# Keyboard.net
KiCad netlist of a schematic drawn in EAGLE
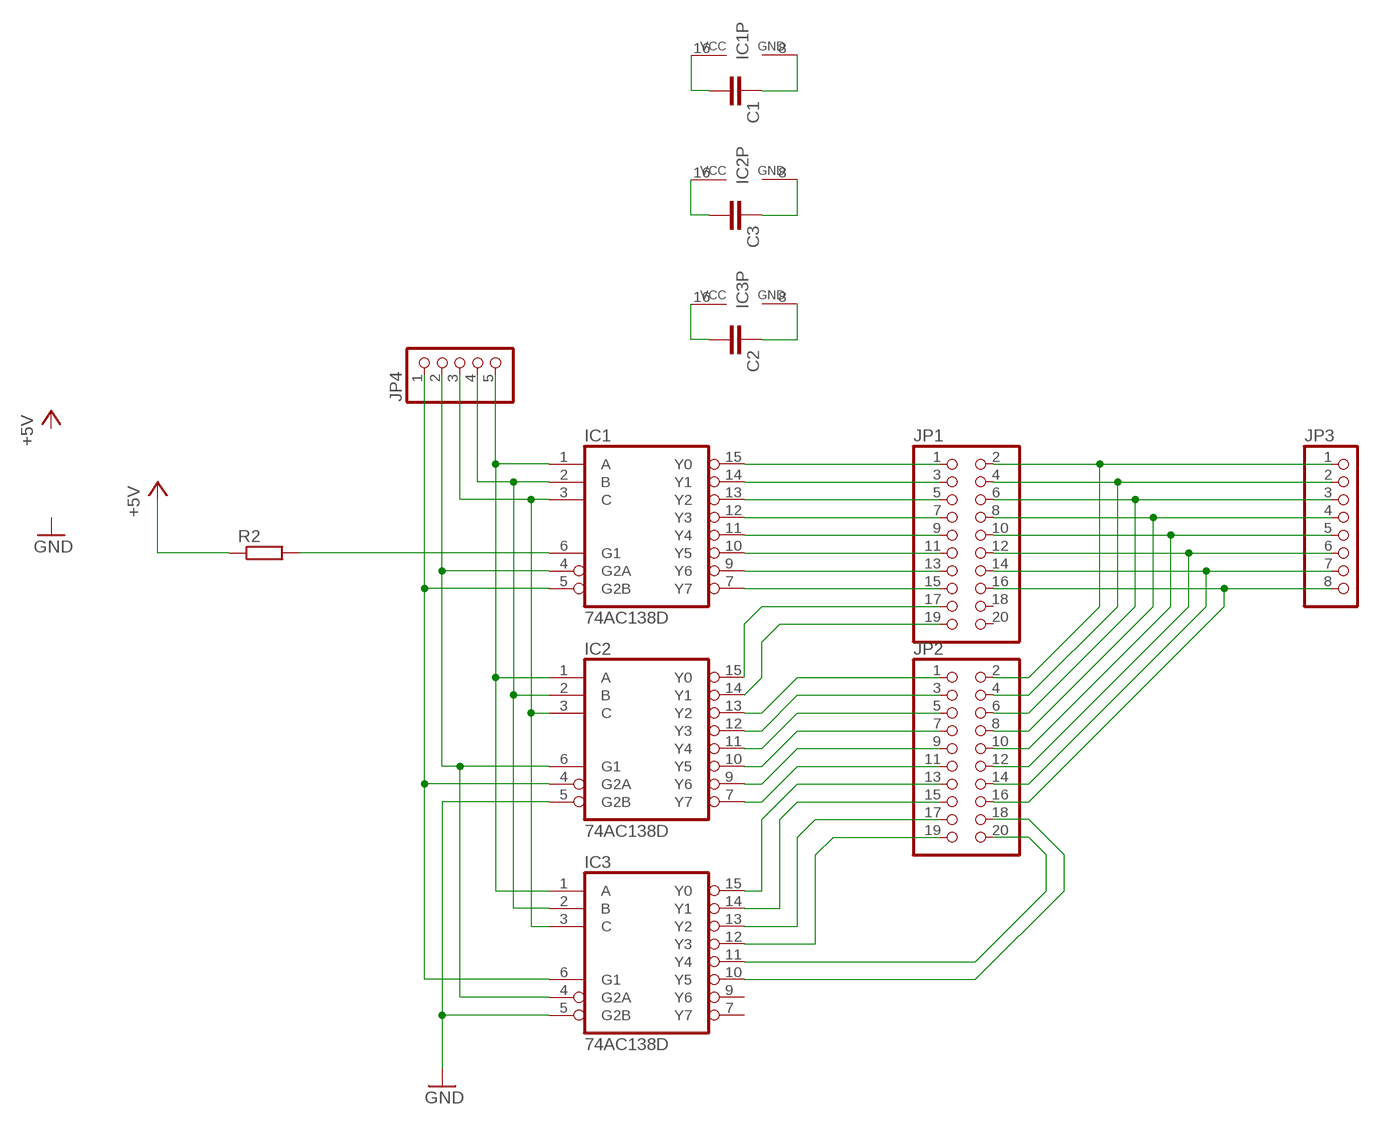
[diagram p0: schematic, sheet 1]

(export (version "E")
  (design (tool "Eeschema 10.0.6"))
  (components
    (comp (ref "C1")
      (value "C-EUC3216")
      (footprint "eagle-import:C3216")
      (libsource (lib "eagle-import") (part "C-EUC3216"))
    )
    (comp (ref "C2")
      (value "C-EUC3216")
      (footprint "eagle-import:C3216")
      (libsource (lib "eagle-import") (part "C-EUC3216"))
    )
    (comp (ref "C3")
      (value "C-EUC3216")
      (footprint "eagle-import:C3216")
      (libsource (lib "eagle-import") (part "C-EUC3216"))
    )
    (comp (ref "IC1")
      (value "74AC138D")
      (footprint "eagle-import:SO16")
      (libsource (lib "eagle-import") (part "74138DAC"))
    )
    (comp (ref "IC2")
      (value "74AC138D")
      (footprint "eagle-import:SO16")
      (libsource (lib "eagle-import") (part "74138DAC"))
    )
    (comp (ref "IC3")
      (value "74AC138D")
      (footprint "eagle-import:SO16")
      (libsource (lib "eagle-import") (part "74138DAC"))
    )
    (comp (ref "JP1")
      (value "PINHD-2X10")
      (footprint "eagle-import:2X10")
      (libsource (lib "eagle-import") (part "PINHD-2X10"))
    )
    (comp (ref "JP2")
      (value "PINHD-2X10")
      (footprint "eagle-import:2X10")
      (libsource (lib "eagle-import") (part "PINHD-2X10"))
    )
    (comp (ref "JP3")
      (value "PINHD-1X8")
      (footprint "eagle-import:1X08")
      (libsource (lib "eagle-import") (part "PINHD-1X8"))
    )
    (comp (ref "JP4")
      (value "PINHD-1X5")
      (footprint "eagle-import:1X05")
      (libsource (lib "eagle-import") (part "PINHD-1X5"))
    )
    (comp (ref "R2")
      (value "R-EU_M3216")
      (footprint "eagle-import:M3216")
      (libsource (lib "eagle-import") (part "R-EU_M3216"))
    )
  )
  (nets
    (net (code "1") (name "+5V") (class "Default")
      (node (ref "R2") (pin "1") (pinfunction "1_1") (pintype "passive"))
    )
    (net (code "2") (name "GND") (class "Default")
      (node (ref "IC2") (pin "5") (pinfunction "G2B_5") (pintype "input"))
      (node (ref "IC3") (pin "5") (pinfunction "G2B_5") (pintype "input"))
    )
    (net (code "3") (name "Net-(IC1A-A)") (class "Default")
      (node (ref "IC1") (pin "1") (pinfunction "A_1") (pintype "input"))
      (node (ref "IC2") (pin "1") (pinfunction "A_1") (pintype "input"))
      (node (ref "IC3") (pin "1") (pinfunction "A_1") (pintype "input"))
      (node (ref "JP4") (pin "5") (pinfunction "5_5") (pintype "passive"))
    )
    (net (code "4") (name "Net-(IC1A-B)") (class "Default")
      (node (ref "IC1") (pin "2") (pinfunction "B_2") (pintype "input"))
      (node (ref "IC2") (pin "2") (pinfunction "B_2") (pintype "input"))
      (node (ref "IC3") (pin "2") (pinfunction "B_2") (pintype "input"))
      (node (ref "JP4") (pin "4") (pinfunction "4_4") (pintype "passive"))
    )
    (net (code "5") (name "Net-(IC1A-C)") (class "Default")
      (node (ref "IC1") (pin "3") (pinfunction "C_3") (pintype "input"))
      (node (ref "IC2") (pin "3") (pinfunction "C_3") (pintype "input"))
      (node (ref "IC3") (pin "3") (pinfunction "C_3") (pintype "input"))
      (node (ref "JP4") (pin "3") (pinfunction "3_3") (pintype "passive"))
    )
    (net (code "6") (name "Net-(IC1A-G1)") (class "Default")
      (node (ref "IC1") (pin "6") (pinfunction "G1_6") (pintype "input"))
      (node (ref "R2") (pin "2") (pinfunction "2_2") (pintype "passive"))
    )
    (net (code "7") (name "Net-(IC1A-G2A)") (class "Default")
      (node (ref "IC1") (pin "4") (pinfunction "G2A_4") (pintype "input"))
      (node (ref "IC2") (pin "6") (pinfunction "G1_6") (pintype "input"))
      (node (ref "IC3") (pin "4") (pinfunction "G2A_4") (pintype "input"))
      (node (ref "JP4") (pin "2") (pinfunction "2_2") (pintype "passive"))
    )
    (net (code "8") (name "Net-(IC1A-G2B)") (class "Default")
      (node (ref "IC1") (pin "5") (pinfunction "G2B_5") (pintype "input"))
      (node (ref "IC2") (pin "4") (pinfunction "G2A_4") (pintype "input"))
      (node (ref "IC3") (pin "6") (pinfunction "G1_6") (pintype "input"))
      (node (ref "JP4") (pin "1") (pinfunction "1_1") (pintype "passive"))
    )
    (net (code "9") (name "Net-(IC1A-Y0)") (class "Default")
      (node (ref "IC1") (pin "15") (pinfunction "Y0_15") (pintype "output"))
      (node (ref "JP1") (pin "1") (pinfunction "1_1") (pintype "passive"))
    )
    (net (code "10") (name "Net-(IC1A-Y1)") (class "Default")
      (node (ref "IC1") (pin "14") (pinfunction "Y1_14") (pintype "output"))
      (node (ref "JP1") (pin "3") (pinfunction "3_3") (pintype "passive"))
    )
    (net (code "11") (name "Net-(IC1A-Y2)") (class "Default")
      (node (ref "IC1") (pin "13") (pinfunction "Y2_13") (pintype "output"))
      (node (ref "JP1") (pin "5") (pinfunction "5_5") (pintype "passive"))
    )
    (net (code "12") (name "Net-(IC1A-Y3)") (class "Default")
      (node (ref "IC1") (pin "12") (pinfunction "Y3_12") (pintype "output"))
      (node (ref "JP1") (pin "7") (pinfunction "7_7") (pintype "passive"))
    )
    (net (code "13") (name "Net-(IC1A-Y4)") (class "Default")
      (node (ref "IC1") (pin "11") (pinfunction "Y4_11") (pintype "output"))
      (node (ref "JP1") (pin "9") (pinfunction "9_9") (pintype "passive"))
    )
    (net (code "14") (name "Net-(IC1A-Y5)") (class "Default")
      (node (ref "IC1") (pin "10") (pinfunction "Y5_10") (pintype "output"))
      (node (ref "JP1") (pin "11") (pinfunction "11_11") (pintype "passive"))
    )
    (net (code "15") (name "Net-(IC1A-Y6)") (class "Default")
      (node (ref "IC1") (pin "9") (pinfunction "Y6_9") (pintype "output"))
      (node (ref "JP1") (pin "13") (pinfunction "13_13") (pintype "passive"))
    )
    (net (code "16") (name "Net-(IC1A-Y7)") (class "Default")
      (node (ref "IC1") (pin "7") (pinfunction "Y7_7") (pintype "output"))
      (node (ref "JP1") (pin "15") (pinfunction "15_15") (pintype "passive"))
    )
    (net (code "17") (name "Net-(IC1B-GND)") (class "Default")
      (node (ref "C1") (pin "1") (pinfunction "1_1") (pintype "passive"))
      (node (ref "IC1") (pin "8") (pinfunction "GND_8") (pintype "power_in"))
    )
    (net (code "18") (name "Net-(IC1B-VCC)") (class "Default")
      (node (ref "C1") (pin "2") (pinfunction "2_2") (pintype "passive"))
      (node (ref "IC1") (pin "16") (pinfunction "VCC_16") (pintype "power_in"))
    )
    (net (code "19") (name "Net-(IC2A-Y0)") (class "Default")
      (node (ref "IC2") (pin "15") (pinfunction "Y0_15") (pintype "output"))
      (node (ref "JP1") (pin "17") (pinfunction "17_17") (pintype "passive"))
    )
    (net (code "20") (name "Net-(IC2A-Y1)") (class "Default")
      (node (ref "IC2") (pin "14") (pinfunction "Y1_14") (pintype "output"))
      (node (ref "JP1") (pin "19") (pinfunction "19_19") (pintype "passive"))
    )
    (net (code "21") (name "Net-(IC2A-Y2)") (class "Default")
      (node (ref "IC2") (pin "13") (pinfunction "Y2_13") (pintype "output"))
      (node (ref "JP2") (pin "1") (pinfunction "1_1") (pintype "passive"))
    )
    (net (code "22") (name "Net-(IC2A-Y3)") (class "Default")
      (node (ref "IC2") (pin "12") (pinfunction "Y3_12") (pintype "output"))
      (node (ref "JP2") (pin "3") (pinfunction "3_3") (pintype "passive"))
    )
    (net (code "23") (name "Net-(IC2A-Y4)") (class "Default")
      (node (ref "IC2") (pin "11") (pinfunction "Y4_11") (pintype "output"))
      (node (ref "JP2") (pin "5") (pinfunction "5_5") (pintype "passive"))
    )
    (net (code "24") (name "Net-(IC2A-Y5)") (class "Default")
      (node (ref "IC2") (pin "10") (pinfunction "Y5_10") (pintype "output"))
      (node (ref "JP2") (pin "7") (pinfunction "7_7") (pintype "passive"))
    )
    (net (code "25") (name "Net-(IC2A-Y6)") (class "Default")
      (node (ref "IC2") (pin "9") (pinfunction "Y6_9") (pintype "output"))
      (node (ref "JP2") (pin "9") (pinfunction "9_9") (pintype "passive"))
    )
    (net (code "26") (name "Net-(IC2A-Y7)") (class "Default")
      (node (ref "IC2") (pin "7") (pinfunction "Y7_7") (pintype "output"))
      (node (ref "JP2") (pin "11") (pinfunction "11_11") (pintype "passive"))
    )
    (net (code "27") (name "Net-(IC2B-GND)") (class "Default")
      (node (ref "C3") (pin "1") (pinfunction "1_1") (pintype "passive"))
      (node (ref "IC2") (pin "8") (pinfunction "GND_8") (pintype "power_in"))
    )
    (net (code "28") (name "Net-(IC2B-VCC)") (class "Default")
      (node (ref "C3") (pin "2") (pinfunction "2_2") (pintype "passive"))
      (node (ref "IC2") (pin "16") (pinfunction "VCC_16") (pintype "power_in"))
    )
    (net (code "29") (name "Net-(IC3A-Y0)") (class "Default")
      (node (ref "IC3") (pin "15") (pinfunction "Y0_15") (pintype "output"))
      (node (ref "JP2") (pin "13") (pinfunction "13_13") (pintype "passive"))
    )
    (net (code "30") (name "Net-(IC3A-Y1)") (class "Default")
      (node (ref "IC3") (pin "14") (pinfunction "Y1_14") (pintype "output"))
      (node (ref "JP2") (pin "15") (pinfunction "15_15") (pintype "passive"))
    )
    (net (code "31") (name "Net-(IC3A-Y2)") (class "Default")
      (node (ref "IC3") (pin "13") (pinfunction "Y2_13") (pintype "output"))
      (node (ref "JP2") (pin "17") (pinfunction "17_17") (pintype "passive"))
    )
    (net (code "32") (name "Net-(IC3A-Y3)") (class "Default")
      (node (ref "IC3") (pin "12") (pinfunction "Y3_12") (pintype "output"))
      (node (ref "JP2") (pin "19") (pinfunction "19_19") (pintype "passive"))
    )
    (net (code "33") (name "Net-(IC3A-Y4)") (class "Default")
      (node (ref "IC3") (pin "11") (pinfunction "Y4_11") (pintype "output"))
      (node (ref "JP2") (pin "20") (pinfunction "20_20") (pintype "passive"))
    )
    (net (code "34") (name "Net-(IC3A-Y5)") (class "Default")
      (node (ref "IC3") (pin "10") (pinfunction "Y5_10") (pintype "output"))
      (node (ref "JP2") (pin "18") (pinfunction "18_18") (pintype "passive"))
    )
    (net (code "35") (name "Net-(IC3B-GND)") (class "Default")
      (node (ref "C2") (pin "1") (pinfunction "1_1") (pintype "passive"))
      (node (ref "IC3") (pin "8") (pinfunction "GND_8") (pintype "power_in"))
    )
    (net (code "36") (name "Net-(IC3B-VCC)") (class "Default")
      (node (ref "C2") (pin "2") (pinfunction "2_2") (pintype "passive"))
      (node (ref "IC3") (pin "16") (pinfunction "VCC_16") (pintype "power_in"))
    )
    (net (code "37") (name "Net-(JP1-Pad2)") (class "Default")
      (node (ref "JP1") (pin "2") (pinfunction "2_2") (pintype "passive"))
      (node (ref "JP2") (pin "2") (pinfunction "2_2") (pintype "passive"))
      (node (ref "JP3") (pin "1") (pinfunction "1_1") (pintype "passive"))
    )
    (net (code "38") (name "Net-(JP1-Pad4)") (class "Default")
      (node (ref "JP1") (pin "4") (pinfunction "4_4") (pintype "passive"))
      (node (ref "JP2") (pin "4") (pinfunction "4_4") (pintype "passive"))
      (node (ref "JP3") (pin "2") (pinfunction "2_2") (pintype "passive"))
    )
    (net (code "39") (name "Net-(JP1-Pad6)") (class "Default")
      (node (ref "JP1") (pin "6") (pinfunction "6_6") (pintype "passive"))
      (node (ref "JP2") (pin "6") (pinfunction "6_6") (pintype "passive"))
      (node (ref "JP3") (pin "3") (pinfunction "3_3") (pintype "passive"))
    )
    (net (code "40") (name "Net-(JP1-Pad8)") (class "Default")
      (node (ref "JP1") (pin "8") (pinfunction "8_8") (pintype "passive"))
      (node (ref "JP2") (pin "8") (pinfunction "8_8") (pintype "passive"))
      (node (ref "JP3") (pin "4") (pinfunction "4_4") (pintype "passive"))
    )
    (net (code "41") (name "Net-(JP1-Pad10)") (class "Default")
      (node (ref "JP1") (pin "10") (pinfunction "10_10") (pintype "passive"))
      (node (ref "JP2") (pin "10") (pinfunction "10_10") (pintype "passive"))
      (node (ref "JP3") (pin "5") (pinfunction "5_5") (pintype "passive"))
    )
    (net (code "42") (name "Net-(JP1-Pad12)") (class "Default")
      (node (ref "JP1") (pin "12") (pinfunction "12_12") (pintype "passive"))
      (node (ref "JP2") (pin "12") (pinfunction "12_12") (pintype "passive"))
      (node (ref "JP3") (pin "6") (pinfunction "6_6") (pintype "passive"))
    )
    (net (code "43") (name "Net-(JP1-Pad14)") (class "Default")
      (node (ref "JP1") (pin "14") (pinfunction "14_14") (pintype "passive"))
      (node (ref "JP2") (pin "14") (pinfunction "14_14") (pintype "passive"))
      (node (ref "JP3") (pin "7") (pinfunction "7_7") (pintype "passive"))
    )
    (net (code "44") (name "Net-(JP1-Pad16)") (class "Default")
      (node (ref "JP1") (pin "16") (pinfunction "16_16") (pintype "passive"))
      (node (ref "JP2") (pin "16") (pinfunction "16_16") (pintype "passive"))
      (node (ref "JP3") (pin "8") (pinfunction "8_8") (pintype "passive"))
    )
    (net (code "45") (name "unconnected-(IC3A-Y6-Pad9)") (class "Default")
      (node (ref "IC3") (pin "9") (pinfunction "Y6_9") (pintype "output"))
    )
    (net (code "46") (name "unconnected-(IC3A-Y7-Pad7)") (class "Default")
      (node (ref "IC3") (pin "7") (pinfunction "Y7_7") (pintype "output"))
    )
    (net (code "47") (name "unconnected-(JP1-Pad18)") (class "Default")
      (node (ref "JP1") (pin "18") (pinfunction "18_18") (pintype "passive"))
    )
    (net (code "48") (name "unconnected-(JP1-Pad20)") (class "Default")
      (node (ref "JP1") (pin "20") (pinfunction "20_20") (pintype "passive"))
    )
  )
)
